# konverter.net
KiCad netlist of a schematic drawn in EAGLE
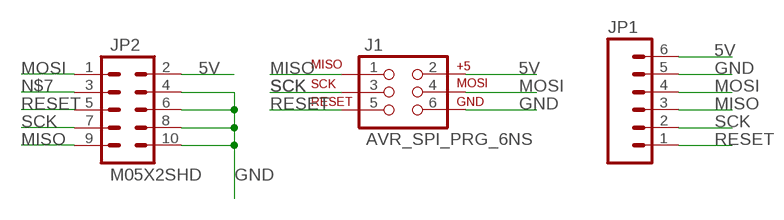
[diagram p0: schematic, sheet 1]

(export (version "E")
  (design (tool "Eeschema 10.0.6"))
  (components
    (comp (ref "J1")
      (value "AVR_SPI_PRG_6NS")
      (footprint "eagle-import:2X3-NS")
      (libsource (lib "eagle-import") (part "AVR_SPI_PRG_6NS"))
    )
    (comp (ref "JP1")
      (value "M06LONGPADS")
      (footprint "eagle-import:1X06_LONGPADS")
      (libsource (lib "eagle-import") (part "M06LONGPADS"))
    )
    (comp (ref "JP2")
      (value "M05X2SHD")
      (footprint "eagle-import:2X5-SHROUDED")
      (libsource (lib "eagle-import") (part "M05X2SHD"))
    )
  )
  (nets
    (net (code "1") (name "/5V") (class "Default")
      (node (ref "J1") (pin "2") (pinfunction "2_2") (pintype "passive"))
      (node (ref "JP1") (pin "6") (pinfunction "6_6") (pintype "passive"))
      (node (ref "JP2") (pin "2") (pinfunction "2_2") (pintype "passive"))
    )
    (net (code "2") (name "/GND") (class "Default")
      (node (ref "J1") (pin "6") (pinfunction "6_6") (pintype "passive"))
      (node (ref "JP1") (pin "5") (pinfunction "5_5") (pintype "passive"))
      (node (ref "JP2") (pin "10") (pinfunction "10_10") (pintype "passive"))
      (node (ref "JP2") (pin "4") (pinfunction "4_4") (pintype "passive"))
      (node (ref "JP2") (pin "6") (pinfunction "6_6") (pintype "passive"))
      (node (ref "JP2") (pin "8") (pinfunction "8_8") (pintype "passive"))
    )
    (net (code "3") (name "/MISO") (class "Default")
      (node (ref "J1") (pin "1") (pinfunction "1_1") (pintype "passive"))
      (node (ref "JP1") (pin "3") (pinfunction "3_3") (pintype "passive"))
      (node (ref "JP2") (pin "9") (pinfunction "9_9") (pintype "passive"))
    )
    (net (code "4") (name "/MOSI") (class "Default")
      (node (ref "J1") (pin "4") (pinfunction "4_4") (pintype "passive"))
      (node (ref "JP1") (pin "4") (pinfunction "4_4") (pintype "passive"))
      (node (ref "JP2") (pin "1") (pinfunction "1_1") (pintype "passive"))
    )
    (net (code "5") (name "/N$7") (class "Default")
      (node (ref "JP2") (pin "3") (pinfunction "3_3") (pintype "passive"))
    )
    (net (code "6") (name "/RESET") (class "Default")
      (node (ref "J1") (pin "5") (pinfunction "5_5") (pintype "passive"))
      (node (ref "JP1") (pin "1") (pinfunction "1_1") (pintype "passive"))
      (node (ref "JP2") (pin "5") (pinfunction "5_5") (pintype "passive"))
    )
    (net (code "7") (name "/SCK") (class "Default")
      (node (ref "J1") (pin "3") (pinfunction "3_3") (pintype "passive"))
      (node (ref "JP1") (pin "2") (pinfunction "2_2") (pintype "passive"))
      (node (ref "JP2") (pin "7") (pinfunction "7_7") (pintype "passive"))
    )
  )
)
